# LEDs_Sheet_1.net
KiCad netlist of a schematic drawn in Altium Designer
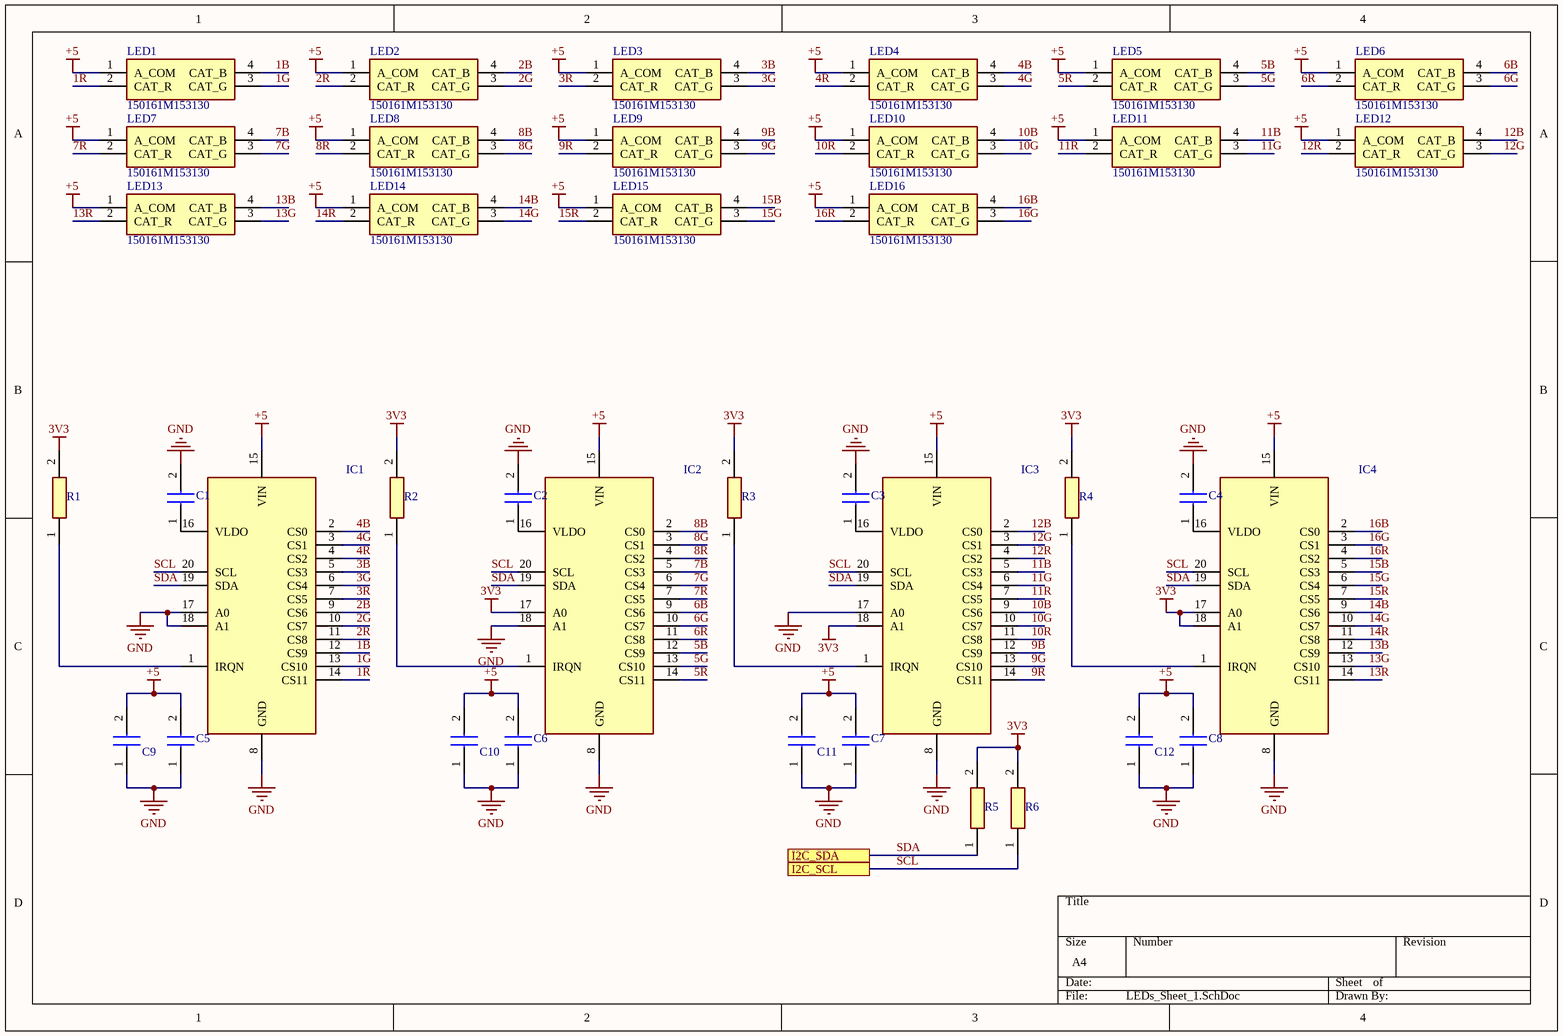
[diagram p0: LEDs_Sheet_1.SchDoc]

(export (version "E")
  (design (tool "Eeschema 10.0.6"))
  (components
    (comp (ref "C1")
      (value "C0402C105K9PAC")
      (footprint "SamacSys:CAPC1005X55N")
      (description "Capacitor")
      (fields (field (name "MOUSER PART NUMBER") "80-C0402C105K9PAC"))
      (libsource (lib "*") (part "C0402C105K9PAC"))
    )
    (comp (ref "C2")
      (value "C0402C105K9PAC")
      (footprint "SamacSys:CAPC1005X55N")
      (description "Capacitor")
      (fields (field (name "MOUSER PART NUMBER") "80-C0402C105K9PAC"))
      (libsource (lib "*") (part "C0402C105K9PAC"))
    )
    (comp (ref "C3")
      (value "C0402C105K9PAC")
      (footprint "SamacSys:CAPC1005X55N")
      (description "Capacitor")
      (fields (field (name "MOUSER PART NUMBER") "80-C0402C105K9PAC"))
      (libsource (lib "*") (part "C0402C105K9PAC"))
    )
    (comp (ref "C4")
      (value "C0402C105K9PAC")
      (footprint "SamacSys:CAPC1005X55N")
      (description "Capacitor")
      (fields (field (name "MOUSER PART NUMBER") "80-C0402C105K9PAC"))
      (libsource (lib "*") (part "C0402C105K9PAC"))
    )
    (comp (ref "C5")
      (value "C0402C105K9PAC")
      (footprint "SamacSys:CAPC1005X55N")
      (description "Capacitor")
      (fields (field (name "MOUSER PART NUMBER") "80-C0402C105K9PAC"))
      (libsource (lib "*") (part "C0402C105K9PAC"))
    )
    (comp (ref "C6")
      (value "C0402C105K9PAC")
      (footprint "SamacSys:CAPC1005X55N")
      (description "Capacitor")
      (fields (field (name "MOUSER PART NUMBER") "80-C0402C105K9PAC"))
      (libsource (lib "*") (part "C0402C105K9PAC"))
    )
    (comp (ref "C7")
      (value "C0402C105K9PAC")
      (footprint "SamacSys:CAPC1005X55N")
      (description "Capacitor")
      (fields (field (name "MOUSER PART NUMBER") "80-C0402C105K9PAC"))
      (libsource (lib "*") (part "C0402C105K9PAC"))
    )
    (comp (ref "C8")
      (value "C0402C105K9PAC")
      (footprint "SamacSys:CAPC1005X55N")
      (description "Capacitor")
      (fields (field (name "MOUSER PART NUMBER") "80-C0402C105K9PAC"))
      (libsource (lib "*") (part "C0402C105K9PAC"))
    )
    (comp (ref "C9")
      (value "C1005X7S1A225K050BC")
      (footprint "PcbLib:C1005_Commercial")
      (description "2µ2F 0402")
      (fields (field (name "MOUSER PART NUMBER") "810-C1005X7S1A225K"))
      (libsource (lib "Schlib") (part "C1005X7S1A225K050BC"))
    )
    (comp (ref "C10")
      (value "C1005X7S1A225K050BC")
      (footprint "PcbLib:C1005_Commercial")
      (description "2µ2F 0402")
      (fields (field (name "MOUSER PART NUMBER") "810-C1005X7S1A225K"))
      (libsource (lib "Schlib") (part "C1005X7S1A225K050BC"))
    )
    (comp (ref "C11")
      (value "C1005X7S1A225K050BC")
      (footprint "PcbLib:C1005_Commercial")
      (description "2µ2F 0402")
      (fields (field (name "MOUSER PART NUMBER") "810-C1005X7S1A225K"))
      (libsource (lib "Schlib") (part "C1005X7S1A225K050BC"))
    )
    (comp (ref "C12")
      (value "C1005X7S1A225K050BC")
      (footprint "PcbLib:C1005_Commercial")
      (description "2µ2F 0402")
      (fields (field (name "MOUSER PART NUMBER") "810-C1005X7S1A225K"))
      (libsource (lib "Schlib") (part "C1005X7S1A225K050BC"))
    )
    (comp (ref "IC1")
      (value "LED1202JR")
      (footprint "PcbLib:QFN20 3x3 (0,5mm pitch)")
      (description "Integrated Circuit")
      (fields (field (name "MOUSER PART NUMBER") "511-LED1202JR"))
      (libsource (lib "Schlib") (part "LED1202JR"))
    )
    (comp (ref "IC2")
      (value "LED1202JR")
      (footprint "PcbLib:QFN20 3x3 (0,5mm pitch)")
      (description "Integrated Circuit")
      (fields (field (name "MOUSER PART NUMBER") "511-LED1202JR"))
      (libsource (lib "Schlib") (part "LED1202JR"))
    )
    (comp (ref "IC3")
      (value "LED1202JR")
      (footprint "PcbLib:QFN20 3x3 (0,5mm pitch)")
      (description "Integrated Circuit")
      (fields (field (name "MOUSER PART NUMBER") "511-LED1202JR"))
      (libsource (lib "Schlib") (part "LED1202JR"))
    )
    (comp (ref "IC4")
      (value "LED1202JR")
      (footprint "PcbLib:QFN20 3x3 (0,5mm pitch)")
      (description "Integrated Circuit")
      (fields (field (name "MOUSER PART NUMBER") "511-LED1202JR"))
      (libsource (lib "Schlib") (part "LED1202JR"))
    )
    (comp (ref "LED1")
      (value "150161M153130")
      (footprint "PcbLib:150161M153130")
      (description "LED")
      (fields (field (name "MOUSER PART NUMBER") "710-150161M153130"))
      (libsource (lib "Schlib") (part "150161M153130"))
    )
    (comp (ref "LED2")
      (value "150161M153130")
      (footprint "PcbLib:150161M153130")
      (description "LED")
      (fields (field (name "MOUSER PART NUMBER") "710-150161M153130"))
      (libsource (lib "Schlib") (part "150161M153130"))
    )
    (comp (ref "LED3")
      (value "150161M153130")
      (footprint "PcbLib:150161M153130")
      (description "LED")
      (fields (field (name "MOUSER PART NUMBER") "710-150161M153130"))
      (libsource (lib "Schlib") (part "150161M153130"))
    )
    (comp (ref "LED4")
      (value "150161M153130")
      (footprint "PcbLib:150161M153130")
      (description "LED")
      (fields (field (name "MOUSER PART NUMBER") "710-150161M153130"))
      (libsource (lib "Schlib") (part "150161M153130"))
    )
    (comp (ref "LED5")
      (value "150161M153130")
      (footprint "PcbLib:150161M153130")
      (description "LED")
      (fields (field (name "MOUSER PART NUMBER") "710-150161M153130"))
      (libsource (lib "Schlib") (part "150161M153130"))
    )
    (comp (ref "LED6")
      (value "150161M153130")
      (footprint "PcbLib:150161M153130")
      (description "LED")
      (fields (field (name "MOUSER PART NUMBER") "710-150161M153130"))
      (libsource (lib "Schlib") (part "150161M153130"))
    )
    (comp (ref "LED7")
      (value "150161M153130")
      (footprint "PcbLib:150161M153130")
      (description "LED")
      (fields (field (name "MOUSER PART NUMBER") "710-150161M153130"))
      (libsource (lib "Schlib") (part "150161M153130"))
    )
    (comp (ref "LED8")
      (value "150161M153130")
      (footprint "PcbLib:150161M153130")
      (description "LED")
      (fields (field (name "MOUSER PART NUMBER") "710-150161M153130"))
      (libsource (lib "Schlib") (part "150161M153130"))
    )
    (comp (ref "LED9")
      (value "150161M153130")
      (footprint "PcbLib:150161M153130")
      (description "LED")
      (fields (field (name "MOUSER PART NUMBER") "710-150161M153130"))
      (libsource (lib "Schlib") (part "150161M153130"))
    )
    (comp (ref "LED10")
      (value "150161M153130")
      (footprint "PcbLib:150161M153130")
      (description "LED")
      (fields (field (name "MOUSER PART NUMBER") "710-150161M153130"))
      (libsource (lib "Schlib") (part "150161M153130"))
    )
    (comp (ref "LED11")
      (value "150161M153130")
      (footprint "PcbLib:150161M153130")
      (description "LED")
      (fields (field (name "MOUSER PART NUMBER") "710-150161M153130"))
      (libsource (lib "Schlib") (part "150161M153130"))
    )
    (comp (ref "LED12")
      (value "150161M153130")
      (footprint "PcbLib:150161M153130")
      (description "LED")
      (fields (field (name "MOUSER PART NUMBER") "710-150161M153130"))
      (libsource (lib "Schlib") (part "150161M153130"))
    )
    (comp (ref "LED13")
      (value "150161M153130")
      (footprint "PcbLib:150161M153130")
      (description "LED")
      (fields (field (name "MOUSER PART NUMBER") "710-150161M153130"))
      (libsource (lib "Schlib") (part "150161M153130"))
    )
    (comp (ref "LED14")
      (value "150161M153130")
      (footprint "PcbLib:150161M153130")
      (description "LED")
      (fields (field (name "MOUSER PART NUMBER") "710-150161M153130"))
      (libsource (lib "Schlib") (part "150161M153130"))
    )
    (comp (ref "LED15")
      (value "150161M153130")
      (footprint "PcbLib:150161M153130")
      (description "LED")
      (fields (field (name "MOUSER PART NUMBER") "710-150161M153130"))
      (libsource (lib "Schlib") (part "150161M153130"))
    )
    (comp (ref "LED16")
      (value "150161M153130")
      (footprint "PcbLib:150161M153130")
      (description "LED")
      (fields (field (name "MOUSER PART NUMBER") "710-150161M153130"))
      (libsource (lib "Schlib") (part "150161M153130"))
    )
    (comp (ref "R1")
      (value "MCS04020D1001BE000")
      (footprint "PcbLib:RESC1005X37N")
      (description "Resistor 1k 0402")
      (fields (field (name "MOUSER PART NUMBER") "594-MCS04020D1001BE0"))
      (libsource (lib "Schlib") (part "MCS04020D1001BE000"))
    )
    (comp (ref "R2")
      (value "MCS04020D1001BE000")
      (footprint "PcbLib:RESC1005X37N")
      (description "Resistor 1k 0402")
      (fields (field (name "MOUSER PART NUMBER") "594-MCS04020D1001BE0"))
      (libsource (lib "Schlib") (part "MCS04020D1001BE000"))
    )
    (comp (ref "R3")
      (value "MCS04020D1001BE000")
      (footprint "PcbLib:RESC1005X37N")
      (description "Resistor 1k 0402")
      (fields (field (name "MOUSER PART NUMBER") "594-MCS04020D1001BE0"))
      (libsource (lib "Schlib") (part "MCS04020D1001BE000"))
    )
    (comp (ref "R4")
      (value "MCS04020D1001BE000")
      (footprint "PcbLib:RESC1005X37N")
      (description "Resistor 1k 0402")
      (fields (field (name "MOUSER PART NUMBER") "594-MCS04020D1001BE0"))
      (libsource (lib "Schlib") (part "MCS04020D1001BE000"))
    )
    (comp (ref "R5")
      (value "MCS04020D1001BE000")
      (footprint "PcbLib:RESC1005X37N")
      (description "Resistor 1k 0402")
      (fields (field (name "MOUSER PART NUMBER") "594-MCS04020D1001BE0"))
      (libsource (lib "Schlib") (part "MCS04020D1001BE000"))
    )
    (comp (ref "R6")
      (value "MCS04020D1001BE000")
      (footprint "PcbLib:RESC1005X37N")
      (description "Resistor 1k 0402")
      (fields (field (name "MOUSER PART NUMBER") "594-MCS04020D1001BE0"))
      (libsource (lib "Schlib") (part "MCS04020D1001BE000"))
    )
  )
  (nets
    (net (code "1") (name "+5") (class "Default")
      (node (ref "C10") (pin "2") (pinfunction "2_2") (pintype "passive"))
      (node (ref "C11") (pin "2") (pinfunction "2_2") (pintype "passive"))
      (node (ref "C12") (pin "2") (pinfunction "2_2") (pintype "passive"))
      (node (ref "C5") (pin "2") (pinfunction "2_2") (pintype "passive"))
      (node (ref "C6") (pin "2") (pinfunction "2_2") (pintype "passive"))
      (node (ref "C7") (pin "2") (pinfunction "2_2") (pintype "passive"))
      (node (ref "C8") (pin "2") (pinfunction "2_2") (pintype "passive"))
      (node (ref "C9") (pin "2") (pinfunction "2_2") (pintype "passive"))
      (node (ref "IC1") (pin "15") (pinfunction "VIN_15") (pintype "passive"))
      (node (ref "IC2") (pin "15") (pinfunction "VIN_15") (pintype "passive"))
      (node (ref "IC3") (pin "15") (pinfunction "VIN_15") (pintype "passive"))
      (node (ref "IC4") (pin "15") (pinfunction "VIN_15") (pintype "passive"))
      (node (ref "LED1") (pin "1") (pinfunction "A_COM_1") (pintype "passive"))
      (node (ref "LED10") (pin "1") (pinfunction "A_COM_1") (pintype "passive"))
      (node (ref "LED11") (pin "1") (pinfunction "A_COM_1") (pintype "passive"))
      (node (ref "LED12") (pin "1") (pinfunction "A_COM_1") (pintype "passive"))
      (node (ref "LED13") (pin "1") (pinfunction "A_COM_1") (pintype "passive"))
      (node (ref "LED14") (pin "1") (pinfunction "A_COM_1") (pintype "passive"))
      (node (ref "LED15") (pin "1") (pinfunction "A_COM_1") (pintype "passive"))
      (node (ref "LED16") (pin "1") (pinfunction "A_COM_1") (pintype "passive"))
      (node (ref "LED2") (pin "1") (pinfunction "A_COM_1") (pintype "passive"))
      (node (ref "LED3") (pin "1") (pinfunction "A_COM_1") (pintype "passive"))
      (node (ref "LED4") (pin "1") (pinfunction "A_COM_1") (pintype "passive"))
      (node (ref "LED5") (pin "1") (pinfunction "A_COM_1") (pintype "passive"))
      (node (ref "LED6") (pin "1") (pinfunction "A_COM_1") (pintype "passive"))
      (node (ref "LED7") (pin "1") (pinfunction "A_COM_1") (pintype "passive"))
      (node (ref "LED8") (pin "1") (pinfunction "A_COM_1") (pintype "passive"))
      (node (ref "LED9") (pin "1") (pinfunction "A_COM_1") (pintype "passive"))
    )
    (net (code "2") (name "/1B") (class "Default")
      (node (ref "IC1") (pin "12") (pinfunction "CS9_12") (pintype "passive"))
      (node (ref "LED1") (pin "4") (pinfunction "CAT_B_4") (pintype "passive"))
    )
    (net (code "3") (name "/1G") (class "Default")
      (node (ref "IC1") (pin "13") (pinfunction "CS10_13") (pintype "passive"))
      (node (ref "LED1") (pin "3") (pinfunction "CAT_G_3") (pintype "passive"))
    )
    (net (code "4") (name "/1R") (class "Default")
      (node (ref "IC1") (pin "14") (pinfunction "CS11_14") (pintype "passive"))
      (node (ref "LED1") (pin "2") (pinfunction "CAT_R_2") (pintype "passive"))
    )
    (net (code "5") (name "/2B") (class "Default")
      (node (ref "IC1") (pin "9") (pinfunction "CS6_9") (pintype "passive"))
      (node (ref "LED2") (pin "4") (pinfunction "CAT_B_4") (pintype "passive"))
    )
    (net (code "6") (name "/2G") (class "Default")
      (node (ref "IC1") (pin "10") (pinfunction "CS7_10") (pintype "passive"))
      (node (ref "LED2") (pin "3") (pinfunction "CAT_G_3") (pintype "passive"))
    )
    (net (code "7") (name "/2R") (class "Default")
      (node (ref "IC1") (pin "11") (pinfunction "CS8_11") (pintype "passive"))
      (node (ref "LED2") (pin "2") (pinfunction "CAT_R_2") (pintype "passive"))
    )
    (net (code "8") (name "/3B") (class "Default")
      (node (ref "IC1") (pin "5") (pinfunction "CS3_5") (pintype "passive"))
      (node (ref "LED3") (pin "4") (pinfunction "CAT_B_4") (pintype "passive"))
    )
    (net (code "9") (name "/3G") (class "Default")
      (node (ref "IC1") (pin "6") (pinfunction "CS4_6") (pintype "passive"))
      (node (ref "LED3") (pin "3") (pinfunction "CAT_G_3") (pintype "passive"))
    )
    (net (code "10") (name "/3R") (class "Default")
      (node (ref "IC1") (pin "7") (pinfunction "CS5_7") (pintype "passive"))
      (node (ref "LED3") (pin "2") (pinfunction "CAT_R_2") (pintype "passive"))
    )
    (net (code "11") (name "/4B") (class "Default")
      (node (ref "IC1") (pin "2") (pinfunction "CS0_2") (pintype "passive"))
      (node (ref "LED4") (pin "4") (pinfunction "CAT_B_4") (pintype "passive"))
    )
    (net (code "12") (name "/4G") (class "Default")
      (node (ref "IC1") (pin "3") (pinfunction "CS1_3") (pintype "passive"))
      (node (ref "LED4") (pin "3") (pinfunction "CAT_G_3") (pintype "passive"))
    )
    (net (code "13") (name "/4R") (class "Default")
      (node (ref "IC1") (pin "4") (pinfunction "CS2_4") (pintype "passive"))
      (node (ref "LED4") (pin "2") (pinfunction "CAT_R_2") (pintype "passive"))
    )
    (net (code "14") (name "/5B") (class "Default")
      (node (ref "IC2") (pin "12") (pinfunction "CS9_12") (pintype "passive"))
      (node (ref "LED5") (pin "4") (pinfunction "CAT_B_4") (pintype "passive"))
    )
    (net (code "15") (name "/5G") (class "Default")
      (node (ref "IC2") (pin "13") (pinfunction "CS10_13") (pintype "passive"))
      (node (ref "LED5") (pin "3") (pinfunction "CAT_G_3") (pintype "passive"))
    )
    (net (code "16") (name "/5R") (class "Default")
      (node (ref "IC2") (pin "14") (pinfunction "CS11_14") (pintype "passive"))
      (node (ref "LED5") (pin "2") (pinfunction "CAT_R_2") (pintype "passive"))
    )
    (net (code "17") (name "/6B") (class "Default")
      (node (ref "IC2") (pin "9") (pinfunction "CS6_9") (pintype "passive"))
      (node (ref "LED6") (pin "4") (pinfunction "CAT_B_4") (pintype "passive"))
    )
    (net (code "18") (name "/6G") (class "Default")
      (node (ref "IC2") (pin "10") (pinfunction "CS7_10") (pintype "passive"))
      (node (ref "LED6") (pin "3") (pinfunction "CAT_G_3") (pintype "passive"))
    )
    (net (code "19") (name "/6R") (class "Default")
      (node (ref "IC2") (pin "11") (pinfunction "CS8_11") (pintype "passive"))
      (node (ref "LED6") (pin "2") (pinfunction "CAT_R_2") (pintype "passive"))
    )
    (net (code "20") (name "/7B") (class "Default")
      (node (ref "IC2") (pin "5") (pinfunction "CS3_5") (pintype "passive"))
      (node (ref "LED7") (pin "4") (pinfunction "CAT_B_4") (pintype "passive"))
    )
    (net (code "21") (name "/7G") (class "Default")
      (node (ref "IC2") (pin "6") (pinfunction "CS4_6") (pintype "passive"))
      (node (ref "LED7") (pin "3") (pinfunction "CAT_G_3") (pintype "passive"))
    )
    (net (code "22") (name "/7R") (class "Default")
      (node (ref "IC2") (pin "7") (pinfunction "CS5_7") (pintype "passive"))
      (node (ref "LED7") (pin "2") (pinfunction "CAT_R_2") (pintype "passive"))
    )
    (net (code "23") (name "/8B") (class "Default")
      (node (ref "IC2") (pin "2") (pinfunction "CS0_2") (pintype "passive"))
      (node (ref "LED8") (pin "4") (pinfunction "CAT_B_4") (pintype "passive"))
    )
    (net (code "24") (name "/8G") (class "Default")
      (node (ref "IC2") (pin "3") (pinfunction "CS1_3") (pintype "passive"))
      (node (ref "LED8") (pin "3") (pinfunction "CAT_G_3") (pintype "passive"))
    )
    (net (code "25") (name "/8R") (class "Default")
      (node (ref "IC2") (pin "4") (pinfunction "CS2_4") (pintype "passive"))
      (node (ref "LED8") (pin "2") (pinfunction "CAT_R_2") (pintype "passive"))
    )
    (net (code "26") (name "/9B") (class "Default")
      (node (ref "IC3") (pin "12") (pinfunction "CS9_12") (pintype "passive"))
      (node (ref "LED9") (pin "4") (pinfunction "CAT_B_4") (pintype "passive"))
    )
    (net (code "27") (name "/9G") (class "Default")
      (node (ref "IC3") (pin "13") (pinfunction "CS10_13") (pintype "passive"))
      (node (ref "LED9") (pin "3") (pinfunction "CAT_G_3") (pintype "passive"))
    )
    (net (code "28") (name "/9R") (class "Default")
      (node (ref "IC3") (pin "14") (pinfunction "CS11_14") (pintype "passive"))
      (node (ref "LED9") (pin "2") (pinfunction "CAT_R_2") (pintype "passive"))
    )
    (net (code "29") (name "/10B") (class "Default")
      (node (ref "IC3") (pin "9") (pinfunction "CS6_9") (pintype "passive"))
      (node (ref "LED10") (pin "4") (pinfunction "CAT_B_4") (pintype "passive"))
    )
    (net (code "30") (name "/10G") (class "Default")
      (node (ref "IC3") (pin "10") (pinfunction "CS7_10") (pintype "passive"))
      (node (ref "LED10") (pin "3") (pinfunction "CAT_G_3") (pintype "passive"))
    )
    (net (code "31") (name "/10R") (class "Default")
      (node (ref "IC3") (pin "11") (pinfunction "CS8_11") (pintype "passive"))
      (node (ref "LED10") (pin "2") (pinfunction "CAT_R_2") (pintype "passive"))
    )
    (net (code "32") (name "/11B") (class "Default")
      (node (ref "IC3") (pin "5") (pinfunction "CS3_5") (pintype "passive"))
      (node (ref "LED11") (pin "4") (pinfunction "CAT_B_4") (pintype "passive"))
    )
    (net (code "33") (name "/11G") (class "Default")
      (node (ref "IC3") (pin "6") (pinfunction "CS4_6") (pintype "passive"))
      (node (ref "LED11") (pin "3") (pinfunction "CAT_G_3") (pintype "passive"))
    )
    (net (code "34") (name "/11R") (class "Default")
      (node (ref "IC3") (pin "7") (pinfunction "CS5_7") (pintype "passive"))
      (node (ref "LED11") (pin "2") (pinfunction "CAT_R_2") (pintype "passive"))
    )
    (net (code "35") (name "/12B") (class "Default")
      (node (ref "IC3") (pin "2") (pinfunction "CS0_2") (pintype "passive"))
      (node (ref "LED12") (pin "4") (pinfunction "CAT_B_4") (pintype "passive"))
    )
    (net (code "36") (name "/12G") (class "Default")
      (node (ref "IC3") (pin "3") (pinfunction "CS1_3") (pintype "passive"))
      (node (ref "LED12") (pin "3") (pinfunction "CAT_G_3") (pintype "passive"))
    )
    (net (code "37") (name "/12R") (class "Default")
      (node (ref "IC3") (pin "4") (pinfunction "CS2_4") (pintype "passive"))
      (node (ref "LED12") (pin "2") (pinfunction "CAT_R_2") (pintype "passive"))
    )
    (net (code "38") (name "/13B") (class "Default")
      (node (ref "IC4") (pin "12") (pinfunction "CS9_12") (pintype "passive"))
      (node (ref "LED13") (pin "4") (pinfunction "CAT_B_4") (pintype "passive"))
    )
    (net (code "39") (name "/13G") (class "Default")
      (node (ref "IC4") (pin "13") (pinfunction "CS10_13") (pintype "passive"))
      (node (ref "LED13") (pin "3") (pinfunction "CAT_G_3") (pintype "passive"))
    )
    (net (code "40") (name "/13R") (class "Default")
      (node (ref "IC4") (pin "14") (pinfunction "CS11_14") (pintype "passive"))
      (node (ref "LED13") (pin "2") (pinfunction "CAT_R_2") (pintype "passive"))
    )
    (net (code "41") (name "/14B") (class "Default")
      (node (ref "IC4") (pin "9") (pinfunction "CS6_9") (pintype "passive"))
      (node (ref "LED14") (pin "4") (pinfunction "CAT_B_4") (pintype "passive"))
    )
    (net (code "42") (name "/14G") (class "Default")
      (node (ref "IC4") (pin "10") (pinfunction "CS7_10") (pintype "passive"))
      (node (ref "LED14") (pin "3") (pinfunction "CAT_G_3") (pintype "passive"))
    )
    (net (code "43") (name "/14R") (class "Default")
      (node (ref "IC4") (pin "11") (pinfunction "CS8_11") (pintype "passive"))
      (node (ref "LED14") (pin "2") (pinfunction "CAT_R_2") (pintype "passive"))
    )
    (net (code "44") (name "/15B") (class "Default")
      (node (ref "IC4") (pin "5") (pinfunction "CS3_5") (pintype "passive"))
      (node (ref "LED15") (pin "4") (pinfunction "CAT_B_4") (pintype "passive"))
    )
    (net (code "45") (name "/15G") (class "Default")
      (node (ref "IC4") (pin "6") (pinfunction "CS4_6") (pintype "passive"))
      (node (ref "LED15") (pin "3") (pinfunction "CAT_G_3") (pintype "passive"))
    )
    (net (code "46") (name "/15R") (class "Default")
      (node (ref "IC4") (pin "7") (pinfunction "CS5_7") (pintype "passive"))
      (node (ref "LED15") (pin "2") (pinfunction "CAT_R_2") (pintype "passive"))
    )
    (net (code "47") (name "/16B") (class "Default")
      (node (ref "IC4") (pin "2") (pinfunction "CS0_2") (pintype "passive"))
      (node (ref "LED16") (pin "4") (pinfunction "CAT_B_4") (pintype "passive"))
    )
    (net (code "48") (name "/16G") (class "Default")
      (node (ref "IC4") (pin "3") (pinfunction "CS1_3") (pintype "passive"))
      (node (ref "LED16") (pin "3") (pinfunction "CAT_G_3") (pintype "passive"))
    )
    (net (code "49") (name "/16R") (class "Default")
      (node (ref "IC4") (pin "4") (pinfunction "CS2_4") (pintype "passive"))
      (node (ref "LED16") (pin "2") (pinfunction "CAT_R_2") (pintype "passive"))
    )
    (net (code "50") (name "/SCL") (class "Default")
      (node (ref "IC1") (pin "20") (pinfunction "SCL_20") (pintype "passive"))
      (node (ref "IC2") (pin "20") (pinfunction "SCL_20") (pintype "passive"))
      (node (ref "IC3") (pin "20") (pinfunction "SCL_20") (pintype "passive"))
      (node (ref "IC4") (pin "20") (pinfunction "SCL_20") (pintype "passive"))
      (node (ref "R6") (pin "1") (pinfunction "1_1") (pintype "passive"))
    )
    (net (code "51") (name "/SDA") (class "Default")
      (node (ref "IC1") (pin "19") (pinfunction "SDA_19") (pintype "passive"))
      (node (ref "IC2") (pin "19") (pinfunction "SDA_19") (pintype "passive"))
      (node (ref "IC3") (pin "19") (pinfunction "SDA_19") (pintype "passive"))
      (node (ref "IC4") (pin "19") (pinfunction "SDA_19") (pintype "passive"))
      (node (ref "R5") (pin "1") (pinfunction "1_1") (pintype "passive"))
    )
    (net (code "52") (name "3V3") (class "Default")
      (node (ref "IC2") (pin "17") (pinfunction "A0_17") (pintype "passive"))
      (node (ref "IC3") (pin "18") (pinfunction "A1_18") (pintype "passive"))
      (node (ref "IC4") (pin "17") (pinfunction "A0_17") (pintype "passive"))
      (node (ref "IC4") (pin "18") (pinfunction "A1_18") (pintype "passive"))
      (node (ref "R1") (pin "2") (pinfunction "2_2") (pintype "passive"))
      (node (ref "R2") (pin "2") (pinfunction "2_2") (pintype "passive"))
      (node (ref "R3") (pin "2") (pinfunction "2_2") (pintype "passive"))
      (node (ref "R4") (pin "2") (pinfunction "2_2") (pintype "passive"))
      (node (ref "R5") (pin "2") (pinfunction "2_2") (pintype "passive"))
      (node (ref "R6") (pin "2") (pinfunction "2_2") (pintype "passive"))
    )
    (net (code "53") (name "GND") (class "Default")
      (node (ref "C1") (pin "2") (pinfunction "2_2") (pintype "passive"))
      (node (ref "C10") (pin "1") (pinfunction "1_1") (pintype "passive"))
      (node (ref "C11") (pin "1") (pinfunction "1_1") (pintype "passive"))
      (node (ref "C12") (pin "1") (pinfunction "1_1") (pintype "passive"))
      (node (ref "C2") (pin "2") (pinfunction "2_2") (pintype "passive"))
      (node (ref "C3") (pin "2") (pinfunction "2_2") (pintype "passive"))
      (node (ref "C4") (pin "2") (pinfunction "2_2") (pintype "passive"))
      (node (ref "C5") (pin "1") (pinfunction "1_1") (pintype "passive"))
      (node (ref "C6") (pin "1") (pinfunction "1_1") (pintype "passive"))
      (node (ref "C7") (pin "1") (pinfunction "1_1") (pintype "passive"))
      (node (ref "C8") (pin "1") (pinfunction "1_1") (pintype "passive"))
      (node (ref "C9") (pin "1") (pinfunction "1_1") (pintype "passive"))
      (node (ref "IC1") (pin "17") (pinfunction "A0_17") (pintype "passive"))
      (node (ref "IC1") (pin "18") (pinfunction "A1_18") (pintype "passive"))
      (node (ref "IC1") (pin "8") (pinfunction "GND_8") (pintype "passive"))
      (node (ref "IC2") (pin "18") (pinfunction "A1_18") (pintype "passive"))
      (node (ref "IC2") (pin "8") (pinfunction "GND_8") (pintype "passive"))
      (node (ref "IC3") (pin "17") (pinfunction "A0_17") (pintype "passive"))
      (node (ref "IC3") (pin "8") (pinfunction "GND_8") (pintype "passive"))
      (node (ref "IC4") (pin "8") (pinfunction "GND_8") (pintype "passive"))
    )
    (net (code "54") (name "Net-(IC1-IRQN)") (class "Default")
      (node (ref "IC1") (pin "1") (pinfunction "IRQN_1") (pintype "passive"))
      (node (ref "R1") (pin "1") (pinfunction "1_1") (pintype "passive"))
    )
    (net (code "55") (name "Net-(IC1-VLDO)") (class "Default")
      (node (ref "C1") (pin "1") (pinfunction "1_1") (pintype "passive"))
      (node (ref "IC1") (pin "16") (pinfunction "VLDO_16") (pintype "passive"))
    )
    (net (code "56") (name "Net-(IC2-IRQN)") (class "Default")
      (node (ref "IC2") (pin "1") (pinfunction "IRQN_1") (pintype "passive"))
      (node (ref "R2") (pin "1") (pinfunction "1_1") (pintype "passive"))
    )
    (net (code "57") (name "Net-(IC2-VLDO)") (class "Default")
      (node (ref "C2") (pin "1") (pinfunction "1_1") (pintype "passive"))
      (node (ref "IC2") (pin "16") (pinfunction "VLDO_16") (pintype "passive"))
    )
    (net (code "58") (name "Net-(IC3-IRQN)") (class "Default")
      (node (ref "IC3") (pin "1") (pinfunction "IRQN_1") (pintype "passive"))
      (node (ref "R3") (pin "1") (pinfunction "1_1") (pintype "passive"))
    )
    (net (code "59") (name "Net-(IC3-VLDO)") (class "Default")
      (node (ref "C3") (pin "1") (pinfunction "1_1") (pintype "passive"))
      (node (ref "IC3") (pin "16") (pinfunction "VLDO_16") (pintype "passive"))
    )
    (net (code "60") (name "Net-(IC4-IRQN)") (class "Default")
      (node (ref "IC4") (pin "1") (pinfunction "IRQN_1") (pintype "passive"))
      (node (ref "R4") (pin "1") (pinfunction "1_1") (pintype "passive"))
    )
    (net (code "61") (name "Net-(IC4-VLDO)") (class "Default")
      (node (ref "C4") (pin "1") (pinfunction "1_1") (pintype "passive"))
      (node (ref "IC4") (pin "16") (pinfunction "VLDO_16") (pintype "passive"))
    )
  )
)
